# ABM8-27_120MHZ-B4-T.net
KiCad netlist of a schematic drawn in Altium Designer
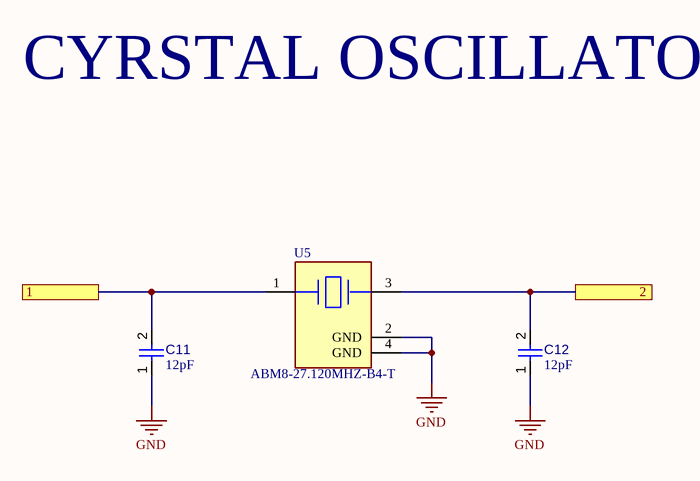
[diagram p0: ABM8-27.120MHZ-B4-T.SchDoc]

(export (version "E")
  (design (tool "Eeschema 10.0.6"))
  (components
    (comp (ref "C11")
      (value "12pF")
      (footprint "CAPC0402(1005)33_L")
      (description "Chip Capacitor, 12pF +/-10%, 50V, 0402, Thickness 0.33 mm")
      (fields (field (name "TOLERANCE") "20%") (field (name "Comment") "Capacitor 12pF +/-10% 50V 0402"))
      (libsource (lib "JCGada") (part "CAP-NP-2"))
    )
    (comp (ref "C12")
      (value "12pF")
      (footprint "CAPC0402(1005)33_L")
      (description "Chip Capacitor, 12pF +/-10%, 50V, 0402, Thickness 0.33 mm")
      (fields (field (name "TOLERANCE") "20%") (field (name "Comment") "Capacitor 12pF +/-10% 50V 0402"))
      (libsource (lib "JCGada") (part "CAP-NP-2"))
    )
    (comp (ref "U5")
      (value "ABM8-27.120MHZ-B4-T")
      (footprint "FP-ABM8-MFG")
      (description "Crystal 27.12MHz ±30ppm 18pF SMD-4 3.2mm x 2.5mm")
      (libsource (lib "Altium Content Vault") (part "dfdb7f9a12507849fb681da9a70121c"))
    )
  )
  (nets
    (net (code "1") (name "/1") (class "Default")
      (node (ref "C11") (pin "2") (pinfunction "2_2") (pintype "passive"))
      (node (ref "U5") (pin "1") (pinfunction "1_1") (pintype "passive"))
    )
    (net (code "2") (name "/2") (class "Default")
      (node (ref "C12") (pin "2") (pinfunction "2_2") (pintype "passive"))
      (node (ref "U5") (pin "3") (pinfunction "3_3") (pintype "passive"))
    )
    (net (code "3") (name "GND") (class "Default")
      (node (ref "C11") (pin "1") (pinfunction "1_1") (pintype "passive"))
      (node (ref "C12") (pin "1") (pinfunction "1_1") (pintype "passive"))
      (node (ref "U5") (pin "2") (pinfunction "GND_2") (pintype "power_in"))
      (node (ref "U5") (pin "4") (pinfunction "GND_4") (pintype "power_in"))
    )
  )
)
